# new.net
KiCad netlist of a schematic drawn in EasyEDA
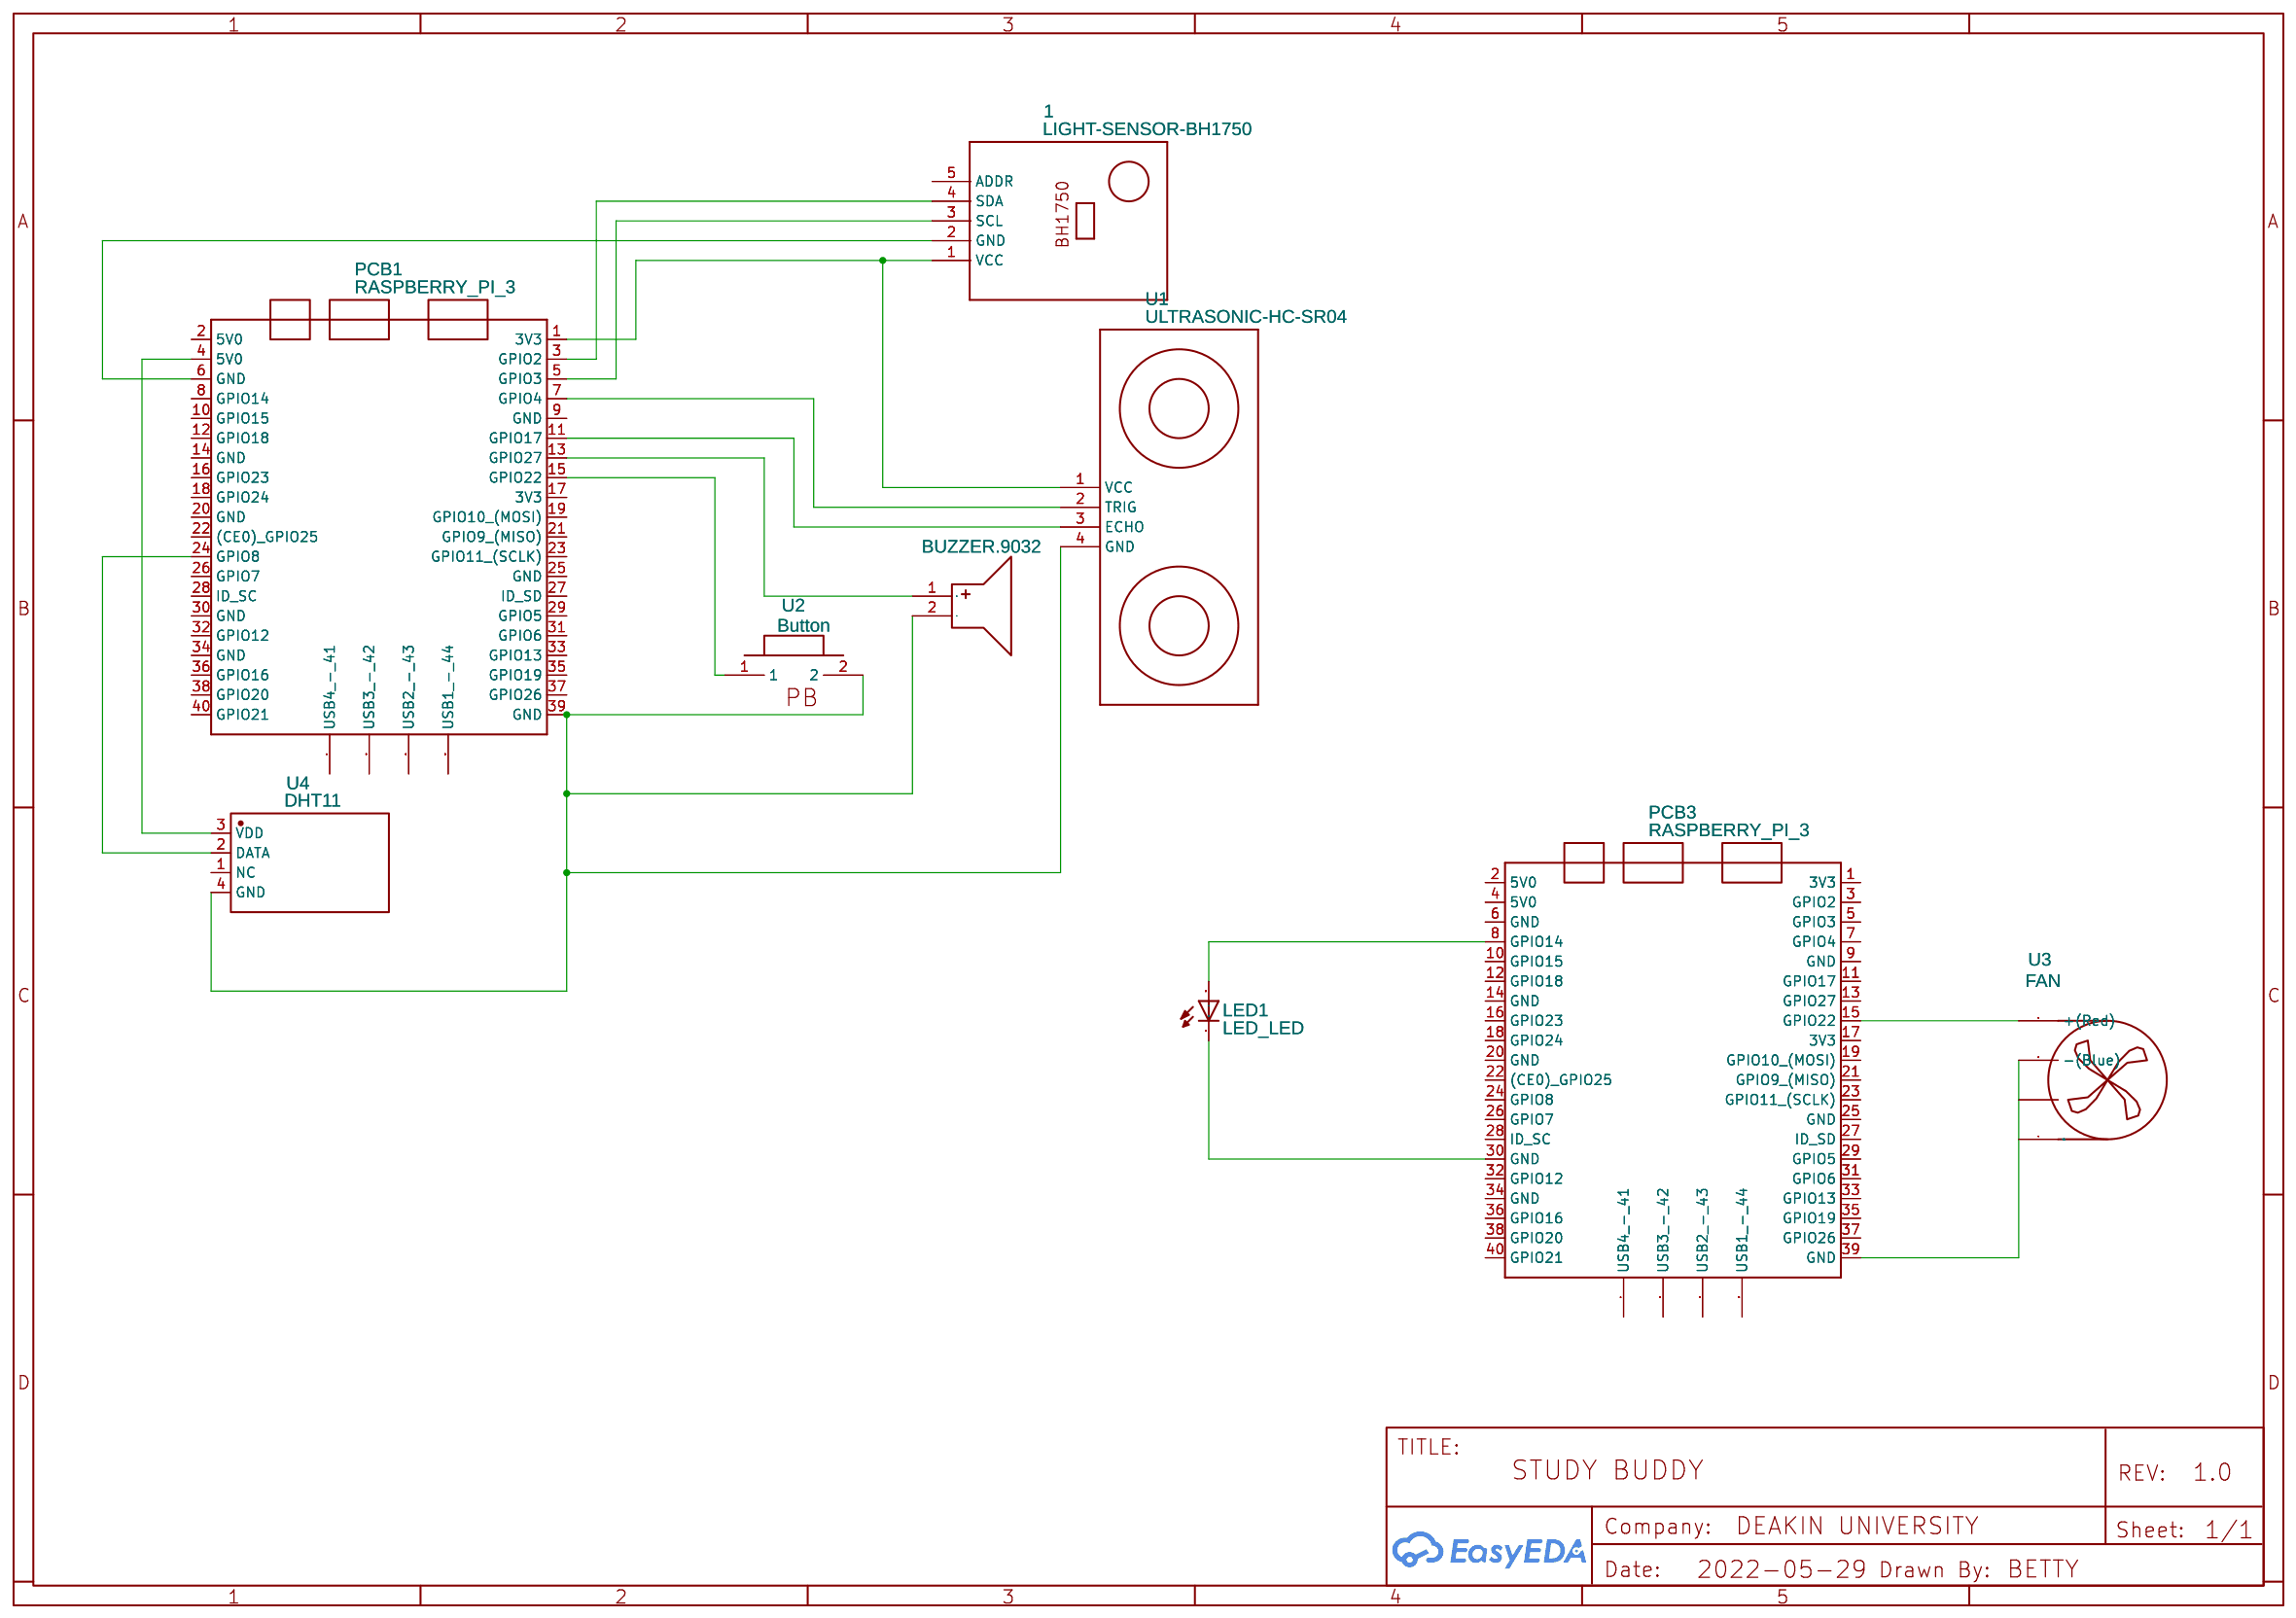
[diagram p0: schematic sheet]

(export (version "E")
  (design (tool "Eeschema 10.0.6"))
  (components
    (comp (ref "1") (value "LIGHT-SENSOR-BH1750") (libsource (lib "") (part "LIGHT-SENSOR-BH1750")))
    (comp (ref "BUZZER1")
      (value "BUZZER.9032")
      (fields (field (name "BOM_Supplier Part") "C9900002564"))
      (libsource (lib "") (part "BUZZER.9032"))
    )
    (comp (ref "LED1") (value "LED_LED") (libsource (lib "") (part "LED_LED")))
    (comp (ref "PCB1") (value "RASPBERRY_PI_3") (libsource (lib "") (part "RASPBERRY_PI_3")))
    (comp (ref "PCB3") (value "RASPBERRY_PI_3") (libsource (lib "") (part "RASPBERRY_PI_3")))
    (comp (ref "U1") (value "ULTRASONIC-HC-SR04") (libsource (lib "") (part "ULTRASONIC-HC-SR04")))
    (comp (ref "U2")
      (value "Button")
      (fields
        (field (name "BOM_Manufacturer Part") "GPTS203211B")
        (field (name "BOM_Supplier Part") "CW181-ND")
      )
      (libsource (lib "") (part "GPTS203211B Push Button On-Off"))
    )
    (comp (ref "U3") (value "FAN") (libsource (lib "") (part "4 PIN FAN")))
    (comp (ref "U4")
      (value "DHT11")
      (fields (field (name "BOM_Supplier Part") "C117051"))
      (libsource (lib "") (part "DHT11"))
    )
  )
  (nets
    (net (code "1") (name "Net-(1-GND)") (class "Default")
      (node (ref "1") (pin "2") (pinfunction "GND_2") (pintype "bidirectional"))
      (node (ref "PCB1") (pin "6") (pinfunction "GND_6") (pintype "unspecified"))
    )
    (net (code "2") (name "Net-(1-SCL)") (class "Default")
      (node (ref "1") (pin "3") (pinfunction "SCL_3") (pintype "bidirectional"))
      (node (ref "PCB1") (pin "5") (pinfunction "GPIO3_5") (pintype "unspecified"))
    )
    (net (code "3") (name "Net-(1-SDA)") (class "Default")
      (node (ref "1") (pin "4") (pinfunction "SDA_4") (pintype "bidirectional"))
      (node (ref "PCB1") (pin "3") (pinfunction "GPIO2_3") (pintype "unspecified"))
    )
    (net (code "4") (name "Net-(1-VCC)") (class "Default")
      (node (ref "1") (pin "1") (pinfunction "VCC_1") (pintype "bidirectional"))
      (node (ref "PCB1") (pin "1") (pinfunction "3V3_1") (pintype "unspecified"))
      (node (ref "U1") (pin "1") (pinfunction "VCC_1") (pintype "passive"))
    )
    (net (code "5") (name "Net-(BUZZER1-+)") (class "Default")
      (node (ref "BUZZER1") (pin "1") (pinfunction "+_1") (pintype "unspecified"))
      (node (ref "PCB1") (pin "13") (pinfunction "GPIO27_13") (pintype "unspecified"))
    )
    (net (code "6") (name "Net-(BUZZER1--)") (class "Default")
      (node (ref "BUZZER1") (pin "2") (pinfunction "-_2") (pintype "unspecified"))
      (node (ref "PCB1") (pin "39") (pinfunction "GND_39") (pintype "unspecified"))
      (node (ref "U1") (pin "4") (pinfunction "GND_4") (pintype "passive"))
      (node (ref "U2") (pin "2") (pinfunction "2_2") (pintype "unspecified"))
      (node (ref "U4") (pin "4") (pinfunction "GND_4") (pintype "unspecified"))
    )
    (net (code "7") (name "Net-(LED1-A)") (class "Default")
      (node (ref "LED1") (pin "A@1") (pinfunction "A_A@1") (pintype "unspecified"))
      (node (ref "PCB3") (pin "8") (pinfunction "GPIO14_8") (pintype "unspecified"))
    )
    (net (code "8") (name "Net-(LED1-C)") (class "Default")
      (node (ref "LED1") (pin "C@1") (pinfunction "C_C@1") (pintype "unspecified"))
      (node (ref "PCB3") (pin "30") (pinfunction "GND_30") (pintype "unspecified"))
    )
    (net (code "9") (name "Net-(PCB1-GPIO4)") (class "Default")
      (node (ref "PCB1") (pin "7") (pinfunction "GPIO4_7") (pintype "unspecified"))
      (node (ref "U1") (pin "2") (pinfunction "TRIG_2") (pintype "input"))
    )
    (net (code "10") (name "Net-(PCB1-GPIO8)") (class "Default")
      (node (ref "PCB1") (pin "24") (pinfunction "GPIO8_24") (pintype "unspecified"))
      (node (ref "U4") (pin "2") (pinfunction "DATA_2") (pintype "unspecified"))
    )
    (net (code "11") (name "Net-(PCB1-GPIO17)") (class "Default")
      (node (ref "PCB1") (pin "11") (pinfunction "GPIO17_11") (pintype "unspecified"))
      (node (ref "U1") (pin "3") (pinfunction "ECHO_3") (pintype "output"))
    )
    (net (code "12") (name "Net-(PCB1-GPIO22)") (class "Default")
      (node (ref "PCB1") (pin "15") (pinfunction "GPIO22_15") (pintype "unspecified"))
      (node (ref "U2") (pin "1") (pinfunction "1_1") (pintype "unspecified"))
    )
    (net (code "13") (name "Net-(PCB3-GPIO22)") (class "Default")
      (node (ref "PCB3") (pin "15") (pinfunction "GPIO22_15") (pintype "unspecified"))
      (node (ref "U3") (pin "1") (pinfunction "+(Red)_1") (pintype "unspecified"))
    )
    (net (code "14") (name "Net-(U3--(Blue))") (class "Default")
      (node (ref "PCB3") (pin "39") (pinfunction "GND_39") (pintype "unspecified"))
      (node (ref "U3") (pin "2") (pinfunction "-(Blue)_2") (pintype "unspecified"))
    )
    (net (code "15") (name "Net-(U4-VDD)") (class "Default")
      (node (ref "PCB1") (pin "4") (pinfunction "5V0_4") (pintype "unspecified"))
      (node (ref "U4") (pin "3") (pinfunction "VDD_3") (pintype "unspecified"))
    )
    (net (code "16") (name "unconnected-(1-ADDR-Pad5)") (class "Default")
      (node (ref "1") (pin "5") (pinfunction "ADDR_5") (pintype "bidirectional"))
    )
    (net (code "17") (name "unconnected-(PCB1-(CE0)_GPIO25-Pad22)") (class "Default")
      (node (ref "PCB1") (pin "22") (pinfunction "(CE0)_GPIO25_22") (pintype "unspecified"))
    )
    (net (code "18") (name "unconnected-(PCB1-3V3-Pad17)") (class "Default")
      (node (ref "PCB1") (pin "17") (pinfunction "3V3_17") (pintype "unspecified"))
    )
    (net (code "19") (name "unconnected-(PCB1-5V0-Pad2)") (class "Default")
      (node (ref "PCB1") (pin "2") (pinfunction "5V0_2") (pintype "unspecified"))
    )
    (net (code "20") (name "unconnected-(PCB1-GND-Pad9)") (class "Default")
      (node (ref "PCB1") (pin "9") (pinfunction "GND_9") (pintype "unspecified"))
    )
    (net (code "21") (name "unconnected-(PCB1-GND-Pad14)") (class "Default")
      (node (ref "PCB1") (pin "14") (pinfunction "GND_14") (pintype "unspecified"))
    )
    (net (code "22") (name "unconnected-(PCB1-GND-Pad20)") (class "Default")
      (node (ref "PCB1") (pin "20") (pinfunction "GND_20") (pintype "unspecified"))
    )
    (net (code "23") (name "unconnected-(PCB1-GND-Pad25)") (class "Default")
      (node (ref "PCB1") (pin "25") (pinfunction "GND_25") (pintype "unspecified"))
    )
    (net (code "24") (name "unconnected-(PCB1-GND-Pad30)") (class "Default")
      (node (ref "PCB1") (pin "30") (pinfunction "GND_30") (pintype "unspecified"))
    )
    (net (code "25") (name "unconnected-(PCB1-GND-Pad34)") (class "Default")
      (node (ref "PCB1") (pin "34") (pinfunction "GND_34") (pintype "unspecified"))
    )
    (net (code "26") (name "unconnected-(PCB1-GPIO5-Pad29)") (class "Default")
      (node (ref "PCB1") (pin "29") (pinfunction "GPIO5_29") (pintype "unspecified"))
    )
    (net (code "27") (name "unconnected-(PCB1-GPIO6-Pad31)") (class "Default")
      (node (ref "PCB1") (pin "31") (pinfunction "GPIO6_31") (pintype "unspecified"))
    )
    (net (code "28") (name "unconnected-(PCB1-GPIO7-Pad26)") (class "Default")
      (node (ref "PCB1") (pin "26") (pinfunction "GPIO7_26") (pintype "unspecified"))
    )
    (net (code "29") (name "unconnected-(PCB1-GPIO9_(MISO)-Pad21)") (class "Default")
      (node (ref "PCB1") (pin "21") (pinfunction "GPIO9_(MISO)_21") (pintype "unspecified"))
    )
    (net (code "30") (name "unconnected-(PCB1-GPIO10_(MOSI)-Pad19)") (class "Default")
      (node (ref "PCB1") (pin "19") (pinfunction "GPIO10_(MOSI)_19") (pintype "unspecified"))
    )
    (net (code "31") (name "unconnected-(PCB1-GPIO11_(SCLK)-Pad23)") (class "Default")
      (node (ref "PCB1") (pin "23") (pinfunction "GPIO11_(SCLK)_23") (pintype "unspecified"))
    )
    (net (code "32") (name "unconnected-(PCB1-GPIO12-Pad32)") (class "Default")
      (node (ref "PCB1") (pin "32") (pinfunction "GPIO12_32") (pintype "unspecified"))
    )
    (net (code "33") (name "unconnected-(PCB1-GPIO13-Pad33)") (class "Default")
      (node (ref "PCB1") (pin "33") (pinfunction "GPIO13_33") (pintype "unspecified"))
    )
    (net (code "34") (name "unconnected-(PCB1-GPIO14-Pad8)") (class "Default")
      (node (ref "PCB1") (pin "8") (pinfunction "GPIO14_8") (pintype "unspecified"))
    )
    (net (code "35") (name "unconnected-(PCB1-GPIO15-Pad10)") (class "Default")
      (node (ref "PCB1") (pin "10") (pinfunction "GPIO15_10") (pintype "unspecified"))
    )
    (net (code "36") (name "unconnected-(PCB1-GPIO16-Pad36)") (class "Default")
      (node (ref "PCB1") (pin "36") (pinfunction "GPIO16_36") (pintype "unspecified"))
    )
    (net (code "37") (name "unconnected-(PCB1-GPIO18-Pad12)") (class "Default")
      (node (ref "PCB1") (pin "12") (pinfunction "GPIO18_12") (pintype "unspecified"))
    )
    (net (code "38") (name "unconnected-(PCB1-GPIO19-Pad35)") (class "Default")
      (node (ref "PCB1") (pin "35") (pinfunction "GPIO19_35") (pintype "unspecified"))
    )
    (net (code "39") (name "unconnected-(PCB1-GPIO20-Pad38)") (class "Default")
      (node (ref "PCB1") (pin "38") (pinfunction "GPIO20_38") (pintype "unspecified"))
    )
    (net (code "40") (name "unconnected-(PCB1-GPIO21-Pad40)") (class "Default")
      (node (ref "PCB1") (pin "40") (pinfunction "GPIO21_40") (pintype "unspecified"))
    )
    (net (code "41") (name "unconnected-(PCB1-GPIO23-Pad16)") (class "Default")
      (node (ref "PCB1") (pin "16") (pinfunction "GPIO23_16") (pintype "unspecified"))
    )
    (net (code "42") (name "unconnected-(PCB1-GPIO24-Pad18)") (class "Default")
      (node (ref "PCB1") (pin "18") (pinfunction "GPIO24_18") (pintype "unspecified"))
    )
    (net (code "43") (name "unconnected-(PCB1-GPIO26-Pad37)") (class "Default")
      (node (ref "PCB1") (pin "37") (pinfunction "GPIO26_37") (pintype "unspecified"))
    )
    (net (code "44") (name "unconnected-(PCB1-ID_SC-Pad28)") (class "Default")
      (node (ref "PCB1") (pin "28") (pinfunction "ID_SC_28") (pintype "unspecified"))
    )
    (net (code "45") (name "unconnected-(PCB1-ID_SD-Pad27)") (class "Default")
      (node (ref "PCB1") (pin "27") (pinfunction "ID_SD_27") (pintype "unspecified"))
    )
    (net (code "46") (name "unconnected-(PCB1-USB1_-_44-Pad46)") (class "Default")
      (node (ref "PCB1") (pin "46") (pinfunction "USB1_-_44_46") (pintype "unspecified"))
    )
    (net (code "47") (name "unconnected-(PCB1-USB2_-_43-Pad43)") (class "Default")
      (node (ref "PCB1") (pin "43") (pinfunction "USB2_-_43_43") (pintype "unspecified"))
    )
    (net (code "48") (name "unconnected-(PCB1-USB3_-_42-Pad45)") (class "Default")
      (node (ref "PCB1") (pin "45") (pinfunction "USB3_-_42_45") (pintype "unspecified"))
    )
    (net (code "49") (name "unconnected-(PCB1-USB4_-_41-Pad44)") (class "Default")
      (node (ref "PCB1") (pin "44") (pinfunction "USB4_-_41_44") (pintype "unspecified"))
    )
    (net (code "50") (name "unconnected-(PCB3-(CE0)_GPIO25-Pad22)") (class "Default")
      (node (ref "PCB3") (pin "22") (pinfunction "(CE0)_GPIO25_22") (pintype "unspecified"))
    )
    (net (code "51") (name "unconnected-(PCB3-3V3-Pad1)") (class "Default")
      (node (ref "PCB3") (pin "1") (pinfunction "3V3_1") (pintype "unspecified"))
    )
    (net (code "52") (name "unconnected-(PCB3-3V3-Pad17)") (class "Default")
      (node (ref "PCB3") (pin "17") (pinfunction "3V3_17") (pintype "unspecified"))
    )
    (net (code "53") (name "unconnected-(PCB3-5V0-Pad2)") (class "Default")
      (node (ref "PCB3") (pin "2") (pinfunction "5V0_2") (pintype "unspecified"))
    )
    (net (code "54") (name "unconnected-(PCB3-5V0-Pad4)") (class "Default")
      (node (ref "PCB3") (pin "4") (pinfunction "5V0_4") (pintype "unspecified"))
    )
    (net (code "55") (name "unconnected-(PCB3-GND-Pad6)") (class "Default")
      (node (ref "PCB3") (pin "6") (pinfunction "GND_6") (pintype "unspecified"))
    )
    (net (code "56") (name "unconnected-(PCB3-GND-Pad9)") (class "Default")
      (node (ref "PCB3") (pin "9") (pinfunction "GND_9") (pintype "unspecified"))
    )
    (net (code "57") (name "unconnected-(PCB3-GND-Pad14)") (class "Default")
      (node (ref "PCB3") (pin "14") (pinfunction "GND_14") (pintype "unspecified"))
    )
    (net (code "58") (name "unconnected-(PCB3-GND-Pad20)") (class "Default")
      (node (ref "PCB3") (pin "20") (pinfunction "GND_20") (pintype "unspecified"))
    )
    (net (code "59") (name "unconnected-(PCB3-GND-Pad25)") (class "Default")
      (node (ref "PCB3") (pin "25") (pinfunction "GND_25") (pintype "unspecified"))
    )
    (net (code "60") (name "unconnected-(PCB3-GND-Pad34)") (class "Default")
      (node (ref "PCB3") (pin "34") (pinfunction "GND_34") (pintype "unspecified"))
    )
    (net (code "61") (name "unconnected-(PCB3-GPIO2-Pad3)") (class "Default")
      (node (ref "PCB3") (pin "3") (pinfunction "GPIO2_3") (pintype "unspecified"))
    )
    (net (code "62") (name "unconnected-(PCB3-GPIO3-Pad5)") (class "Default")
      (node (ref "PCB3") (pin "5") (pinfunction "GPIO3_5") (pintype "unspecified"))
    )
    (net (code "63") (name "unconnected-(PCB3-GPIO4-Pad7)") (class "Default")
      (node (ref "PCB3") (pin "7") (pinfunction "GPIO4_7") (pintype "unspecified"))
    )
    (net (code "64") (name "unconnected-(PCB3-GPIO5-Pad29)") (class "Default")
      (node (ref "PCB3") (pin "29") (pinfunction "GPIO5_29") (pintype "unspecified"))
    )
    (net (code "65") (name "unconnected-(PCB3-GPIO6-Pad31)") (class "Default")
      (node (ref "PCB3") (pin "31") (pinfunction "GPIO6_31") (pintype "unspecified"))
    )
    (net (code "66") (name "unconnected-(PCB3-GPIO7-Pad26)") (class "Default")
      (node (ref "PCB3") (pin "26") (pinfunction "GPIO7_26") (pintype "unspecified"))
    )
    (net (code "67") (name "unconnected-(PCB3-GPIO8-Pad24)") (class "Default")
      (node (ref "PCB3") (pin "24") (pinfunction "GPIO8_24") (pintype "unspecified"))
    )
    (net (code "68") (name "unconnected-(PCB3-GPIO9_(MISO)-Pad21)") (class "Default")
      (node (ref "PCB3") (pin "21") (pinfunction "GPIO9_(MISO)_21") (pintype "unspecified"))
    )
    (net (code "69") (name "unconnected-(PCB3-GPIO10_(MOSI)-Pad19)") (class "Default")
      (node (ref "PCB3") (pin "19") (pinfunction "GPIO10_(MOSI)_19") (pintype "unspecified"))
    )
    (net (code "70") (name "unconnected-(PCB3-GPIO11_(SCLK)-Pad23)") (class "Default")
      (node (ref "PCB3") (pin "23") (pinfunction "GPIO11_(SCLK)_23") (pintype "unspecified"))
    )
    (net (code "71") (name "unconnected-(PCB3-GPIO12-Pad32)") (class "Default")
      (node (ref "PCB3") (pin "32") (pinfunction "GPIO12_32") (pintype "unspecified"))
    )
    (net (code "72") (name "unconnected-(PCB3-GPIO13-Pad33)") (class "Default")
      (node (ref "PCB3") (pin "33") (pinfunction "GPIO13_33") (pintype "unspecified"))
    )
    (net (code "73") (name "unconnected-(PCB3-GPIO15-Pad10)") (class "Default")
      (node (ref "PCB3") (pin "10") (pinfunction "GPIO15_10") (pintype "unspecified"))
    )
    (net (code "74") (name "unconnected-(PCB3-GPIO16-Pad36)") (class "Default")
      (node (ref "PCB3") (pin "36") (pinfunction "GPIO16_36") (pintype "unspecified"))
    )
    (net (code "75") (name "unconnected-(PCB3-GPIO17-Pad11)") (class "Default")
      (node (ref "PCB3") (pin "11") (pinfunction "GPIO17_11") (pintype "unspecified"))
    )
    (net (code "76") (name "unconnected-(PCB3-GPIO18-Pad12)") (class "Default")
      (node (ref "PCB3") (pin "12") (pinfunction "GPIO18_12") (pintype "unspecified"))
    )
    (net (code "77") (name "unconnected-(PCB3-GPIO19-Pad35)") (class "Default")
      (node (ref "PCB3") (pin "35") (pinfunction "GPIO19_35") (pintype "unspecified"))
    )
    (net (code "78") (name "unconnected-(PCB3-GPIO20-Pad38)") (class "Default")
      (node (ref "PCB3") (pin "38") (pinfunction "GPIO20_38") (pintype "unspecified"))
    )
    (net (code "79") (name "unconnected-(PCB3-GPIO21-Pad40)") (class "Default")
      (node (ref "PCB3") (pin "40") (pinfunction "GPIO21_40") (pintype "unspecified"))
    )
    (net (code "80") (name "unconnected-(PCB3-GPIO23-Pad16)") (class "Default")
      (node (ref "PCB3") (pin "16") (pinfunction "GPIO23_16") (pintype "unspecified"))
    )
    (net (code "81") (name "unconnected-(PCB3-GPIO24-Pad18)") (class "Default")
      (node (ref "PCB3") (pin "18") (pinfunction "GPIO24_18") (pintype "unspecified"))
    )
    (net (code "82") (name "unconnected-(PCB3-GPIO26-Pad37)") (class "Default")
      (node (ref "PCB3") (pin "37") (pinfunction "GPIO26_37") (pintype "unspecified"))
    )
    (net (code "83") (name "unconnected-(PCB3-GPIO27-Pad13)") (class "Default")
      (node (ref "PCB3") (pin "13") (pinfunction "GPIO27_13") (pintype "unspecified"))
    )
    (net (code "84") (name "unconnected-(PCB3-ID_SC-Pad28)") (class "Default")
      (node (ref "PCB3") (pin "28") (pinfunction "ID_SC_28") (pintype "unspecified"))
    )
    (net (code "85") (name "unconnected-(PCB3-ID_SD-Pad27)") (class "Default")
      (node (ref "PCB3") (pin "27") (pinfunction "ID_SD_27") (pintype "unspecified"))
    )
    (net (code "86") (name "unconnected-(PCB3-USB1_-_44-Pad46)") (class "Default")
      (node (ref "PCB3") (pin "46") (pinfunction "USB1_-_44_46") (pintype "unspecified"))
    )
    (net (code "87") (name "unconnected-(PCB3-USB2_-_43-Pad43)") (class "Default")
      (node (ref "PCB3") (pin "43") (pinfunction "USB2_-_43_43") (pintype "unspecified"))
    )
    (net (code "88") (name "unconnected-(PCB3-USB3_-_42-Pad45)") (class "Default")
      (node (ref "PCB3") (pin "45") (pinfunction "USB3_-_42_45") (pintype "unspecified"))
    )
    (net (code "89") (name "unconnected-(PCB3-USB4_-_41-Pad44)") (class "Default")
      (node (ref "PCB3") (pin "44") (pinfunction "USB4_-_41_44") (pintype "unspecified"))
    )
    (net (code "90") (name "unconnected-(U3-Pad)") (class "Default")
      (node (ref "U3") (pin "") (pintype "unspecified"))
    )
    (net (code "91") (name "unconnected-(U3-Tac_(White)-Pad4)") (class "Default")
      (node (ref "U3") (pin "4") (pinfunction "Tac_(White)_4") (pintype "unspecified"))
    )
    (net (code "92") (name "unconnected-(U4-NC-Pad1)") (class "Default")
      (node (ref "U4") (pin "1") (pinfunction "NC_1") (pintype "unspecified"))
    )
  )
)
